# PIIzza_TIme.net
KiCad netlist of a schematic drawn in EAGLE
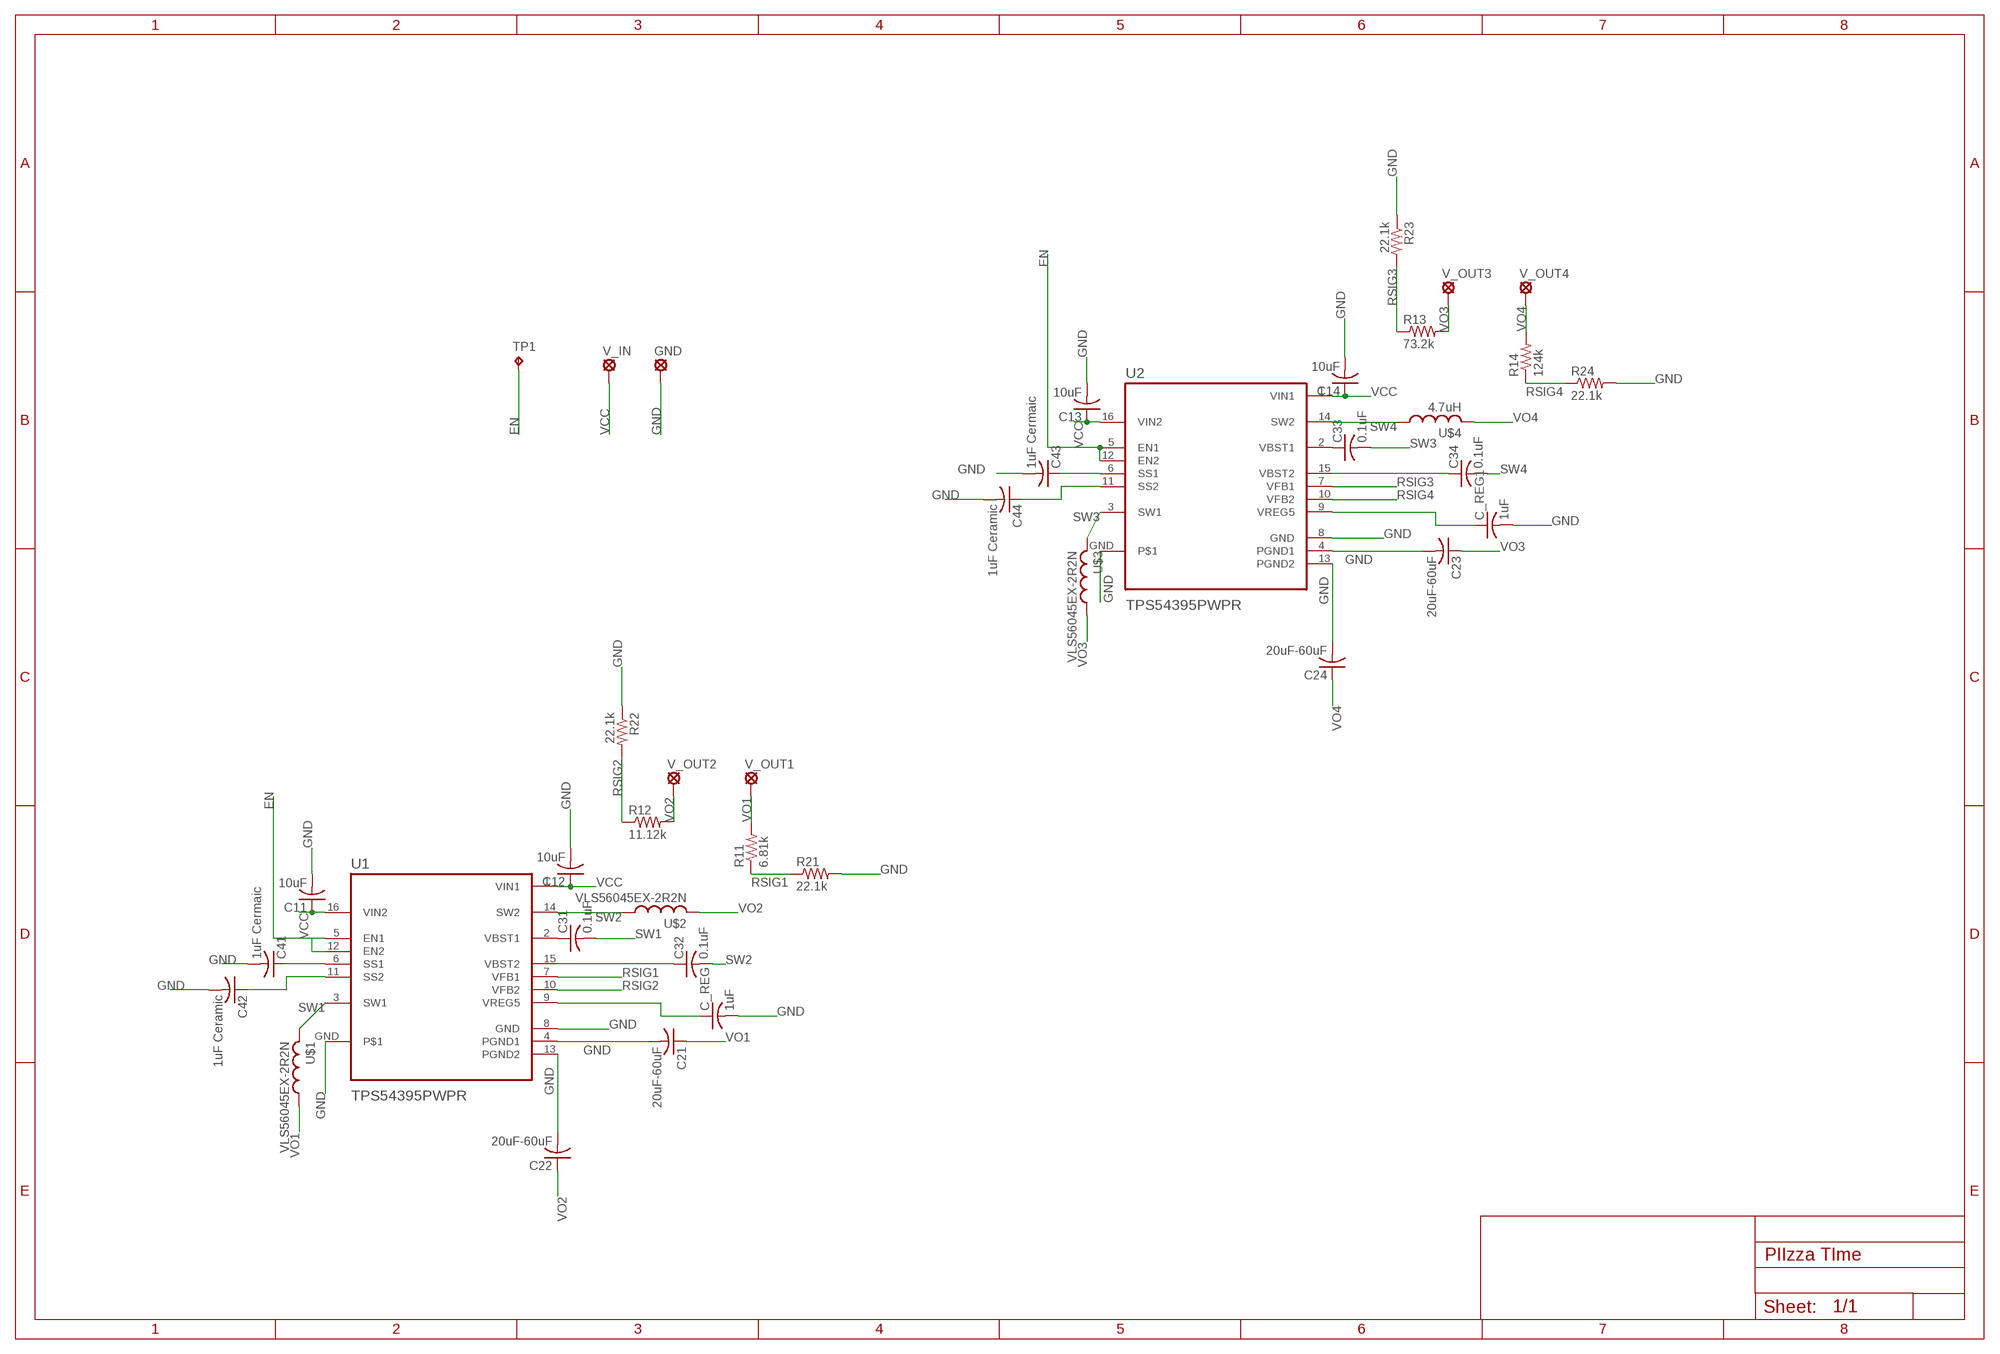
[diagram p0: schematic, sheet 1]

(export (version "E")
  (design (tool "Eeschema 10.0.6"))
  (components
    (comp (ref "C11")
      (value "10uF")
      (footprint "eagle-import:C0805")
      (libsource (lib "eagle-import") (part "C-USC0805"))
    )
    (comp (ref "C12")
      (value "10uF")
      (footprint "eagle-import:C0805")
      (libsource (lib "eagle-import") (part "C-USC0805"))
    )
    (comp (ref "C13")
      (value "10uF")
      (footprint "eagle-import:C0805")
      (libsource (lib "eagle-import") (part "C-USC0805"))
    )
    (comp (ref "C14")
      (value "10uF")
      (footprint "eagle-import:C0805")
      (libsource (lib "eagle-import") (part "C-USC0805"))
    )
    (comp (ref "C21")
      (value "20uF-60uF")
      (footprint "eagle-import:C0805")
      (libsource (lib "eagle-import") (part "C-USC0805"))
    )
    (comp (ref "C22")
      (value "20uF-60uF")
      (footprint "eagle-import:C0805")
      (libsource (lib "eagle-import") (part "C-USC0805"))
    )
    (comp (ref "C23")
      (value "20uF-60uF")
      (footprint "eagle-import:C0805")
      (libsource (lib "eagle-import") (part "C-USC0805"))
    )
    (comp (ref "C24")
      (value "20uF-60uF")
      (footprint "eagle-import:C0805")
      (libsource (lib "eagle-import") (part "C-USC0805"))
    )
    (comp (ref "C31")
      (value "0.1uF")
      (footprint "eagle-import:C0805")
      (libsource (lib "eagle-import") (part "C-USC0805"))
    )
    (comp (ref "C32")
      (value "0.1uF")
      (footprint "eagle-import:C0805")
      (libsource (lib "eagle-import") (part "C-USC0805"))
    )
    (comp (ref "C33")
      (value "0.1uF")
      (footprint "eagle-import:C0805")
      (libsource (lib "eagle-import") (part "C-USC0805"))
    )
    (comp (ref "C34")
      (value "0.1uF")
      (footprint "eagle-import:C0805")
      (libsource (lib "eagle-import") (part "C-USC0805"))
    )
    (comp (ref "C41")
      (value "1uF Cermaic")
      (footprint "eagle-import:C0805")
      (libsource (lib "eagle-import") (part "C-USC0805"))
    )
    (comp (ref "C42")
      (value "1uF Ceramic")
      (footprint "eagle-import:C0805")
      (libsource (lib "eagle-import") (part "C-USC0805"))
    )
    (comp (ref "C43")
      (value "1uF Cermaic")
      (footprint "eagle-import:C0805")
      (libsource (lib "eagle-import") (part "C-USC0805"))
    )
    (comp (ref "C44")
      (value "1uF Ceramic")
      (footprint "eagle-import:C0805")
      (libsource (lib "eagle-import") (part "C-USC0805"))
    )
    (comp (ref "C_REG")
      (value "1uF")
      (footprint "eagle-import:C0805")
      (libsource (lib "eagle-import") (part "C-USC0805"))
    )
    (comp (ref "C_REG1")
      (value "1uF")
      (footprint "eagle-import:C0805")
      (libsource (lib "eagle-import") (part "C-USC0805"))
    )
    (comp (ref "GND")
      (value "SE11")
      (footprint "eagle-import:SE11")
      (libsource (lib "eagle-import") (part "SE11"))
    )
    (comp (ref "R11")
      (value "6.81k")
      (footprint "eagle-import:M0805")
      (libsource (lib "eagle-import") (part "R-US_M0805"))
    )
    (comp (ref "R12")
      (value "11.12k")
      (footprint "eagle-import:M0805")
      (libsource (lib "eagle-import") (part "R-US_M0805"))
    )
    (comp (ref "R13")
      (value "73.2k")
      (footprint "eagle-import:M0805")
      (libsource (lib "eagle-import") (part "R-US_M0805"))
    )
    (comp (ref "R14")
      (value "124k")
      (footprint "eagle-import:M0805")
      (libsource (lib "eagle-import") (part "R-US_M0805"))
    )
    (comp (ref "R21")
      (value "22.1k")
      (footprint "eagle-import:M0805")
      (libsource (lib "eagle-import") (part "R-US_M0805"))
    )
    (comp (ref "R22")
      (value "22.1k")
      (footprint "eagle-import:M0805")
      (libsource (lib "eagle-import") (part "R-US_M0805"))
    )
    (comp (ref "R23")
      (value "22.1k")
      (footprint "eagle-import:M0805")
      (libsource (lib "eagle-import") (part "R-US_M0805"))
    )
    (comp (ref "R24")
      (value "22.1k")
      (footprint "eagle-import:M0805")
      (libsource (lib "eagle-import") (part "R-US_M0805"))
    )
    (comp (ref "TP1")
      (value "TPB1,27")
      (footprint "eagle-import:B1,27")
      (libsource (lib "eagle-import") (part "TPB1,27"))
    )
    (comp (ref "U$1")
      (value "VLS56045EX-2R2N")
      (footprint "eagle-import:VLS")
      (libsource (lib "eagle-import") (part "VLS56045EX-2R2N"))
    )
    (comp (ref "U$2")
      (value "VLS56045EX-2R2N")
      (footprint "eagle-import:VLS")
      (libsource (lib "eagle-import") (part "VLS56045EX-2R2N"))
    )
    (comp (ref "U$3")
      (value "VLS56045EX-2R2N")
      (footprint "eagle-import:VLS")
      (libsource (lib "eagle-import") (part "VLS56045EX-2R2N"))
    )
    (comp (ref "U$4")
      (value "4.7uH")
      (footprint "eagle-import:VLS")
      (libsource (lib "eagle-import") (part "VLS56045EX-2R2N"))
    )
    (comp (ref "U1")
      (value "TPS54395PWPR")
      (footprint "eagle-import:SOP65P640X120-17N")
      (fields (field (name "MF") "Texas Instruments"))
      (libsource (lib "eagle-import") (part "TPS54395PWPR"))
    )
    (comp (ref "U2")
      (value "TPS54395PWPR")
      (footprint "eagle-import:SOP65P640X120-17N")
      (fields (field (name "MF") "Texas Instruments"))
      (libsource (lib "eagle-import") (part "TPS54395PWPR"))
    )
    (comp (ref "V_IN")
      (value "LSP11")
      (footprint "eagle-import:LSP11")
      (libsource (lib "eagle-import") (part "LSP11"))
    )
    (comp (ref "V_OUT1")
      (value "LSP11")
      (footprint "eagle-import:LSP11")
      (libsource (lib "eagle-import") (part "LSP11"))
    )
    (comp (ref "V_OUT2")
      (value "LSP11")
      (footprint "eagle-import:LSP11")
      (libsource (lib "eagle-import") (part "LSP11"))
    )
    (comp (ref "V_OUT3")
      (value "LSP11")
      (footprint "eagle-import:LSP11")
      (libsource (lib "eagle-import") (part "LSP11"))
    )
    (comp (ref "V_OUT4")
      (value "LSP11")
      (footprint "eagle-import:LSP11")
      (libsource (lib "eagle-import") (part "LSP11"))
    )
  )
  (nets
    (net (code "1") (name "/EN") (class "Default")
      (node (ref "TP1") (pin "TP") (pinfunction "TP_TP") (pintype "input"))
      (node (ref "U1") (pin "12") (pinfunction "EN2_12") (pintype "bidirectional"))
      (node (ref "U1") (pin "5") (pinfunction "EN1_5") (pintype "bidirectional"))
      (node (ref "U2") (pin "12") (pinfunction "EN2_12") (pintype "bidirectional"))
      (node (ref "U2") (pin "5") (pinfunction "EN1_5") (pintype "bidirectional"))
    )
    (net (code "2") (name "/GND") (class "Default")
      (node (ref "C11") (pin "2") (pinfunction "2_2") (pintype "passive"))
      (node (ref "C12") (pin "2") (pinfunction "2_2") (pintype "passive"))
      (node (ref "C13") (pin "2") (pinfunction "2_2") (pintype "passive"))
      (node (ref "C14") (pin "2") (pinfunction "2_2") (pintype "passive"))
      (node (ref "C21") (pin "2") (pinfunction "2_2") (pintype "passive"))
      (node (ref "C22") (pin "2") (pinfunction "2_2") (pintype "passive"))
      (node (ref "C23") (pin "2") (pinfunction "2_2") (pintype "passive"))
      (node (ref "C24") (pin "2") (pinfunction "2_2") (pintype "passive"))
      (node (ref "C41") (pin "2") (pinfunction "2_2") (pintype "passive"))
      (node (ref "C42") (pin "2") (pinfunction "2_2") (pintype "passive"))
      (node (ref "C43") (pin "2") (pinfunction "2_2") (pintype "passive"))
      (node (ref "C44") (pin "2") (pinfunction "2_2") (pintype "passive"))
      (node (ref "C_REG") (pin "2") (pinfunction "2_2") (pintype "passive"))
      (node (ref "C_REG1") (pin "2") (pinfunction "2_2") (pintype "passive"))
      (node (ref "GND") (pin "MP") (pinfunction "MP_MP") (pintype "passive"))
      (node (ref "R21") (pin "2") (pinfunction "2_2") (pintype "passive"))
      (node (ref "R22") (pin "1") (pinfunction "1_1") (pintype "passive"))
      (node (ref "R23") (pin "1") (pinfunction "1_1") (pintype "passive"))
      (node (ref "R24") (pin "2") (pinfunction "2_2") (pintype "passive"))
      (node (ref "U1") (pin "13") (pinfunction "PGND2_13") (pintype "power_in"))
      (node (ref "U1") (pin "4") (pinfunction "PGND1_4") (pintype "power_in"))
      (node (ref "U1") (pin "8") (pinfunction "GND_8") (pintype "power_in"))
      (node (ref "U1") (pin "GND") (pinfunction "P$1_GND") (pintype "bidirectional"))
      (node (ref "U2") (pin "13") (pinfunction "PGND2_13") (pintype "power_in"))
      (node (ref "U2") (pin "4") (pinfunction "PGND1_4") (pintype "power_in"))
      (node (ref "U2") (pin "8") (pinfunction "GND_8") (pintype "power_in"))
      (node (ref "U2") (pin "GND") (pinfunction "P$1_GND") (pintype "bidirectional"))
    )
    (net (code "3") (name "/RSIG1") (class "Default")
      (node (ref "R11") (pin "1") (pinfunction "1_1") (pintype "passive"))
      (node (ref "R21") (pin "1") (pinfunction "1_1") (pintype "passive"))
      (node (ref "U1") (pin "7") (pinfunction "VFB1_7") (pintype "bidirectional"))
    )
    (net (code "4") (name "/RSIG2") (class "Default")
      (node (ref "R12") (pin "1") (pinfunction "1_1") (pintype "passive"))
      (node (ref "R22") (pin "2") (pinfunction "2_2") (pintype "passive"))
      (node (ref "U1") (pin "10") (pinfunction "VFB2_10") (pintype "bidirectional"))
    )
    (net (code "5") (name "/RSIG3") (class "Default")
      (node (ref "R13") (pin "1") (pinfunction "1_1") (pintype "passive"))
      (node (ref "R23") (pin "2") (pinfunction "2_2") (pintype "passive"))
      (node (ref "U2") (pin "7") (pinfunction "VFB1_7") (pintype "bidirectional"))
    )
    (net (code "6") (name "/RSIG4") (class "Default")
      (node (ref "R14") (pin "1") (pinfunction "1_1") (pintype "passive"))
      (node (ref "R24") (pin "1") (pinfunction "1_1") (pintype "passive"))
      (node (ref "U2") (pin "10") (pinfunction "VFB2_10") (pintype "bidirectional"))
    )
    (net (code "7") (name "/SW1") (class "Default")
      (node (ref "C31") (pin "2") (pinfunction "2_2") (pintype "passive"))
      (node (ref "U$1") (pin "P$2") (pinfunction "2_P$2") (pintype "passive"))
      (node (ref "U1") (pin "3") (pinfunction "SW1_3") (pintype "bidirectional"))
    )
    (net (code "8") (name "/SW2") (class "Default")
      (node (ref "C32") (pin "2") (pinfunction "2_2") (pintype "passive"))
      (node (ref "U$2") (pin "P$1") (pinfunction "1_P$1") (pintype "passive"))
      (node (ref "U1") (pin "14") (pinfunction "SW2_14") (pintype "bidirectional"))
    )
    (net (code "9") (name "/SW3") (class "Default")
      (node (ref "C33") (pin "2") (pinfunction "2_2") (pintype "passive"))
      (node (ref "U$3") (pin "P$2") (pinfunction "2_P$2") (pintype "passive"))
      (node (ref "U2") (pin "3") (pinfunction "SW1_3") (pintype "bidirectional"))
    )
    (net (code "10") (name "/SW4") (class "Default")
      (node (ref "C34") (pin "2") (pinfunction "2_2") (pintype "passive"))
      (node (ref "U$4") (pin "P$1") (pinfunction "1_P$1") (pintype "passive"))
      (node (ref "U2") (pin "14") (pinfunction "SW2_14") (pintype "bidirectional"))
    )
    (net (code "11") (name "/VCC") (class "Default")
      (node (ref "C11") (pin "1") (pinfunction "1_1") (pintype "passive"))
      (node (ref "C12") (pin "1") (pinfunction "1_1") (pintype "passive"))
      (node (ref "C13") (pin "1") (pinfunction "1_1") (pintype "passive"))
      (node (ref "C14") (pin "1") (pinfunction "1_1") (pintype "passive"))
      (node (ref "U1") (pin "1") (pinfunction "VIN1_1") (pintype "power_in"))
      (node (ref "U1") (pin "16") (pinfunction "VIN2_16") (pintype "input"))
      (node (ref "U2") (pin "1") (pinfunction "VIN1_1") (pintype "power_in"))
      (node (ref "U2") (pin "16") (pinfunction "VIN2_16") (pintype "input"))
      (node (ref "V_IN") (pin "MP") (pinfunction "MP_MP") (pintype "passive"))
    )
    (net (code "12") (name "/VO1") (class "Default")
      (node (ref "C21") (pin "1") (pinfunction "1_1") (pintype "passive"))
      (node (ref "R11") (pin "2") (pinfunction "2_2") (pintype "passive"))
      (node (ref "U$1") (pin "P$1") (pinfunction "1_P$1") (pintype "passive"))
      (node (ref "V_OUT1") (pin "MP") (pinfunction "MP_MP") (pintype "passive"))
    )
    (net (code "13") (name "/VO2") (class "Default")
      (node (ref "C22") (pin "1") (pinfunction "1_1") (pintype "passive"))
      (node (ref "R12") (pin "2") (pinfunction "2_2") (pintype "passive"))
      (node (ref "U$2") (pin "P$2") (pinfunction "2_P$2") (pintype "passive"))
      (node (ref "V_OUT2") (pin "MP") (pinfunction "MP_MP") (pintype "passive"))
    )
    (net (code "14") (name "/VO3") (class "Default")
      (node (ref "C23") (pin "1") (pinfunction "1_1") (pintype "passive"))
      (node (ref "R13") (pin "2") (pinfunction "2_2") (pintype "passive"))
      (node (ref "U$3") (pin "P$1") (pinfunction "1_P$1") (pintype "passive"))
      (node (ref "V_OUT3") (pin "MP") (pinfunction "MP_MP") (pintype "passive"))
    )
    (net (code "15") (name "/VO4") (class "Default")
      (node (ref "C24") (pin "1") (pinfunction "1_1") (pintype "passive"))
      (node (ref "R14") (pin "2") (pinfunction "2_2") (pintype "passive"))
      (node (ref "U$4") (pin "P$2") (pinfunction "2_P$2") (pintype "passive"))
      (node (ref "V_OUT4") (pin "MP") (pinfunction "MP_MP") (pintype "passive"))
    )
    (net (code "16") (name "Net-(U1-SS1)") (class "Default")
      (node (ref "C41") (pin "1") (pinfunction "1_1") (pintype "passive"))
      (node (ref "U1") (pin "6") (pinfunction "SS1_6") (pintype "bidirectional"))
    )
    (net (code "17") (name "Net-(U1-SS2)") (class "Default")
      (node (ref "C42") (pin "1") (pinfunction "1_1") (pintype "passive"))
      (node (ref "U1") (pin "11") (pinfunction "SS2_11") (pintype "bidirectional"))
    )
    (net (code "18") (name "Net-(U1-VBST1)") (class "Default")
      (node (ref "C31") (pin "1") (pinfunction "1_1") (pintype "passive"))
      (node (ref "U1") (pin "2") (pinfunction "VBST1_2") (pintype "bidirectional"))
    )
    (net (code "19") (name "Net-(U1-VBST2)") (class "Default")
      (node (ref "C32") (pin "1") (pinfunction "1_1") (pintype "passive"))
      (node (ref "U1") (pin "15") (pinfunction "VBST2_15") (pintype "bidirectional"))
    )
    (net (code "20") (name "Net-(U1-VREG5)") (class "Default")
      (node (ref "C_REG") (pin "1") (pinfunction "1_1") (pintype "passive"))
      (node (ref "U1") (pin "9") (pinfunction "VREG5_9") (pintype "bidirectional"))
    )
    (net (code "21") (name "Net-(U2-SS1)") (class "Default")
      (node (ref "C43") (pin "1") (pinfunction "1_1") (pintype "passive"))
      (node (ref "U2") (pin "6") (pinfunction "SS1_6") (pintype "bidirectional"))
    )
    (net (code "22") (name "Net-(U2-SS2)") (class "Default")
      (node (ref "C44") (pin "1") (pinfunction "1_1") (pintype "passive"))
      (node (ref "U2") (pin "11") (pinfunction "SS2_11") (pintype "bidirectional"))
    )
    (net (code "23") (name "Net-(U2-VBST1)") (class "Default")
      (node (ref "C33") (pin "1") (pinfunction "1_1") (pintype "passive"))
      (node (ref "U2") (pin "2") (pinfunction "VBST1_2") (pintype "bidirectional"))
    )
    (net (code "24") (name "Net-(U2-VBST2)") (class "Default")
      (node (ref "C34") (pin "1") (pinfunction "1_1") (pintype "passive"))
      (node (ref "U2") (pin "15") (pinfunction "VBST2_15") (pintype "bidirectional"))
    )
    (net (code "25") (name "Net-(U2-VREG5)") (class "Default")
      (node (ref "C_REG1") (pin "1") (pinfunction "1_1") (pintype "passive"))
      (node (ref "U2") (pin "9") (pinfunction "VREG5_9") (pintype "bidirectional"))
    )
  )
)
